# CAN.net
KiCad netlist of a schematic drawn in Altium Designer
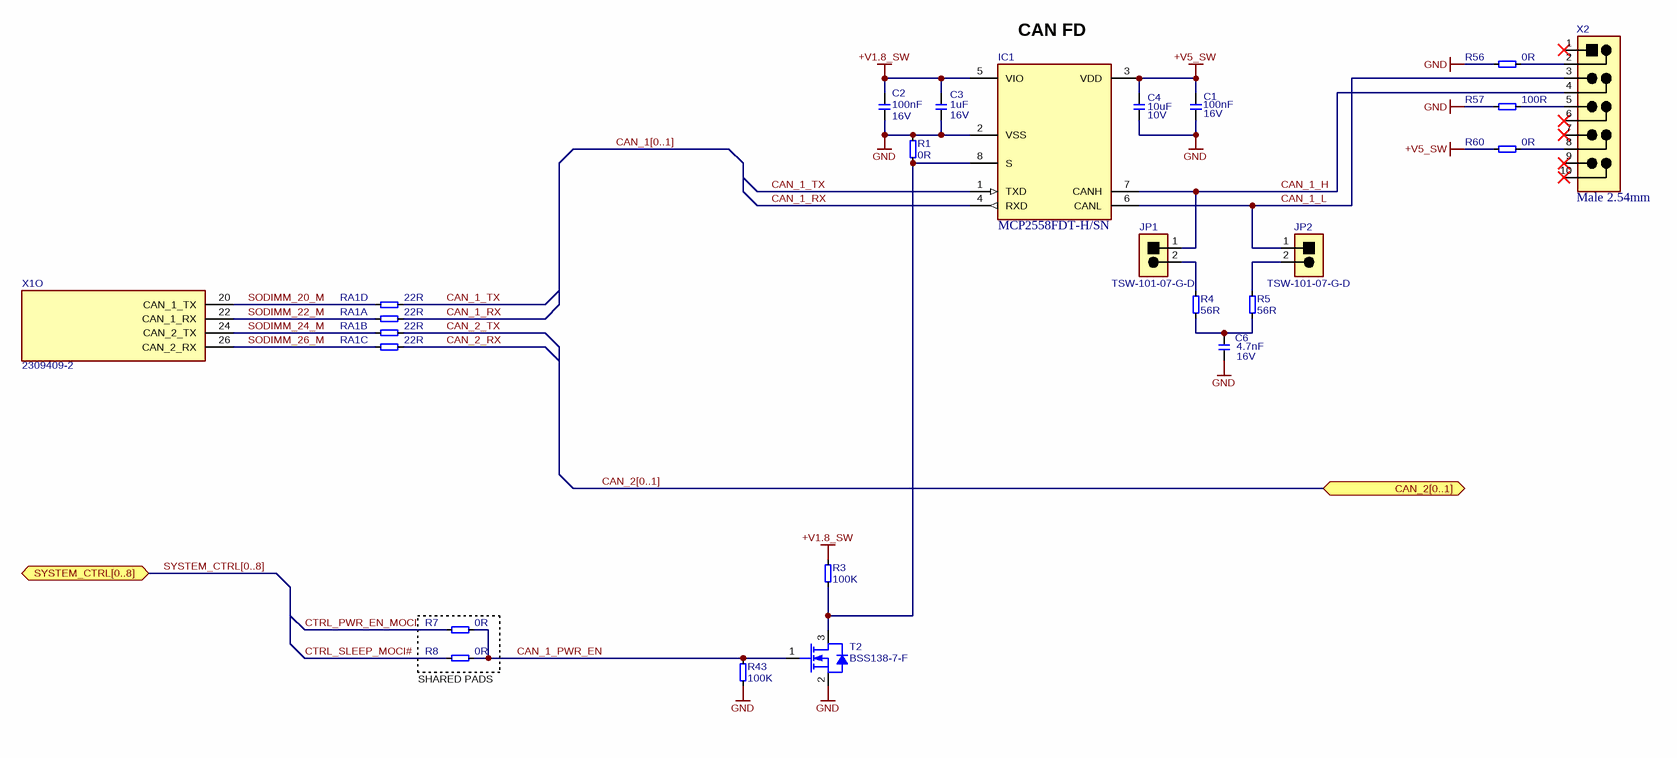
[diagram p0: CAN.SchDoc]

(export (version "E")
  (design (tool "Eeschema 10.0.6"))
  (components
    (comp (ref "C1")
      (value "100nF")
      (footprint "CAPC1005X60N")
      (description "Capacitor Ceramic X7R 100nF 16V 10% 0402")
      (fields (field (name "TOLERANCE") "10%") (field (name "RATING") "16V"))
      (libsource (lib "Dahlia Carrier Board") (part "C-X7R-100nF-16V-10%-0402"))
    )
    (comp (ref "C2")
      (value "100nF")
      (footprint "CAPC1005X60N")
      (description "Capacitor Ceramic X7R 100nF 16V 10% 0402")
      (fields (field (name "TOLERANCE") "10%") (field (name "RATING") "16V"))
      (libsource (lib "Dahlia Carrier Board") (part "C-X7R-100nF-16V-10%-0402"))
    )
    (comp (ref "C3")
      (value "1uF")
      (footprint "CAPC1005X60N")
      (description "Capacitor Ceramic X5R 1uF 16V 20% 0402")
      (fields (field (name "TOLERANCE") "20%") (field (name "RATING") "16V"))
      (libsource (lib "Dahlia Carrier Board") (part "C-X5R-1uF-16V-20%-0402"))
    )
    (comp (ref "C4")
      (value "10uF")
      (footprint "T_CAPC0603X33N")
      (description "Capacitor Ceramic X5R 10uF 10V 20% 0603")
      (fields (field (name "TOLERANCE") "20%") (field (name "RATING") "10V"))
      (libsource (lib "Dahlia Carrier Board") (part "C-X5R-10uF-10V-20%-0603"))
    )
    (comp (ref "C6")
      (value "4.7nF")
      (footprint "T_CAPC0603X33N")
      (description "Capacitor Ceramic X7R 4.7nF 16V 10% 0603")
      (fields (field (name "TOLERANCE") "10%") (field (name "RATING") "16V"))
      (libsource (lib "Dahlia Carrier Board") (part "C-X7R-4.7nF-16V-10%-0603"))
    )
    (comp (ref "IC1")
      (value "MCP2558FDT-H/SN")
      (footprint "IC-SOIC-8")
      (description "CAN FD Transceiver with Silent Mode")
      (fields (field (name "MANUFACTURER PART NO.") "MCP2558FDT-H/SN"))
      (libsource (lib "Dahlia Carrier Board") (part "IC-Microchip-MCP2558FDT-H/SN"))
    )
    (comp (ref "JP1")
      (value "TSW-101-07-G-D")
      (footprint "T_Samtec_TSW-101-07-G-D")
      (description "Header male, 1x2 Pins, 2.54 mm pitch")
      (libsource (lib "Dahlia Carrier Board") (part "CON-Samtec-TSW-101-07-G-D"))
    )
    (comp (ref "JP2")
      (value "TSW-101-07-G-D")
      (footprint "T_Samtec_TSW-101-07-G-D")
      (description "Header male, 1x2 Pins, 2.54 mm pitch")
      (libsource (lib "") (part "CON-Samtec-TSW-101-07-G-D_1"))
    )
    (comp (ref "R1")
      (value "0R")
      (footprint "T_RESC0603X30N")
      (description "Resistor 0 ohm 63mW 1% 0603")
      (fields (field (name "TOLERANCE") "1%"))
      (libsource (lib "Dahlia Carrier Board") (part "R-0R-63mW-1%-0603"))
    )
    (comp (ref "R3")
      (value "100K")
      (footprint "RESC1005X40N")
      (description "Resistor 100 Kohm 63mW 5% 0402")
      (fields (field (name "TOLERANCE") "5%"))
      (libsource (lib "Dahlia Carrier Board") (part "R-100K-63mW-5%-0402"))
    )
    (comp (ref "R4")
      (value "56R")
      (footprint "T_RESC0603X30N")
      (description "Resistor 56 ohm 125mW 1% 0603")
      (fields (field (name "TOLERANCE") "1%"))
      (libsource (lib "Dahlia Carrier Board") (part "R-56R-125mW-1%-0603"))
    )
    (comp (ref "R5")
      (value "56R")
      (footprint "T_RESC0603X30N")
      (description "Resistor 56 ohm 125mW 1% 0603")
      (fields (field (name "TOLERANCE") "1%"))
      (libsource (lib "Dahlia Carrier Board") (part "R-56R-125mW-1%-0603"))
    )
    (comp (ref "R7")
      (value "0R")
      (footprint "T_RESC0603X30N")
      (description "Resistor 0 ohm 63mW 1% 0603")
      (fields (field (name "TOLERANCE") "1%"))
      (libsource (lib "Dahlia Carrier Board") (part "R-0R-63mW-1%-0603"))
    )
    (comp (ref "R8")
      (value "0R")
      (footprint "T_RESC0603X30N")
      (description "Resistor 0 ohm 63mW 1% 0603")
      (fields (field (name "TOLERANCE") "1%"))
      (libsource (lib "Dahlia Carrier Board") (part "R-0R-63mW-1%-0603"))
    )
    (comp (ref "R43")
      (value "100K")
      (footprint "RESC1005X40N")
      (description "Resistor 100 Kohm 63mW 5% 0402")
      (fields (field (name "TOLERANCE") "5%"))
      (libsource (lib "Dahlia Carrier Board") (part "R-100K-63mW-5%-0402"))
    )
    (comp (ref "R56")
      (value "0R")
      (footprint "T_RESC0603X30N")
      (description "Resistor 0 ohm 63mW 1% 0603")
      (fields (field (name "TOLERANCE") "1%"))
      (libsource (lib "Dahlia Carrier Board") (part "R-0R-63mW-1%-0603"))
    )
    (comp (ref "R57")
      (value "100R")
      (footprint "T_RESC0603X30N")
      (description "Resistor 100 ohm 63mW 5% 0603")
      (fields (field (name "TOLERANCE") "5%"))
      (libsource (lib "Dahlia Carrier Board") (part "R-100R-63mW-5%-0603"))
    )
    (comp (ref "R60")
      (value "0R")
      (footprint "T_RESC0603X30N")
      (description "Resistor 0 ohm 63mW 1% 0603")
      (fields (field (name "TOLERANCE") "1%"))
      (libsource (lib "Dahlia Carrier Board") (part "R-0R-63mW-1%-0603"))
    )
    (comp (ref "RA1")
      (value "22R")
      (footprint "T_Resistor_Array_X4")
      (description "Resistor Array 22 R 63mW 5% 1206")
      (fields (field (name "TOLERANCE") "5%"))
      (libsource (lib "Dahlia Carrier Board") (part "RA-22R-63mW-5%-1206-div"))
    )
    (comp (ref "T2")
      (value "BSS138-7-F")
      (footprint "SOT95P237X112-3N")
      (description "N-channel MOSFET, BSS138-7-F")
      (fields (field (name "MANUFACTURER PART NO.") "BSS138-7-F"))
      (libsource (lib "Dahlia Carrier Board") (part "T-Diodes-BSS138-7-F"))
    )
    (comp (ref "X1")
      (value "2309409-2")
      (footprint "CON-TE-2309409-2-SOLDERABLE-STANDOFFS")
      (description "DDR4 SODIMM Socket, 260 pins, 5.2mm(H), 0.5mm Pitch")
      (libsource (lib "Dahlia Carrier Board") (part "CON-TE-2309409-2"))
    )
    (comp (ref "X2")
      (value "Male 2.54mm")
      (footprint "CON-Header-2x5-Male-2.54mm")
      (description "Header Male, 2x5 Pins, 2.54mm pitch")
      (fields (field (name "MANUFACTURER PART NO.") "77313-101-10LF"))
      (libsource (lib "Dahlia Carrier Board") (part "CON-Header-2x5-Male-2.54mm"))
    )
  )
  (nets
    (net (code "14") (name "+V1.8_SW") (class "Default")
      (node (ref "C2") (pin "2") (pinfunction "2_2") (pintype "passive"))
      (node (ref "C3") (pin "2") (pinfunction "2_2") (pintype "passive"))
      (node (ref "IC1") (pin "5") (pinfunction "VIO_5") (pintype "passive"))
      (node (ref "R3") (pin "1") (pinfunction "1_1") (pintype "passive"))
    )
    (net (code "15") (name "+V5_SW") (class "Default")
      (node (ref "C1") (pin "2") (pinfunction "2_2") (pintype "passive"))
      (node (ref "C4") (pin "2") (pinfunction "2_2") (pintype "passive"))
      (node (ref "IC1") (pin "3") (pinfunction "VDD_3") (pintype "power_in"))
      (node (ref "R60") (pin "2") (pinfunction "2_2") (pintype "passive"))
    )
    (net (code "17") (name "/CAN_1_H") (class "Default")
      (node (ref "IC1") (pin "7") (pinfunction "CANH_7") (pintype "passive"))
      (node (ref "JP1") (pin "1") (pinfunction "1_1") (pintype "passive"))
      (node (ref "X2") (pin "4") (pinfunction "4_4") (pintype "passive"))
    )
    (net (code "18") (name "/CAN_1_L") (class "Default")
      (node (ref "IC1") (pin "6") (pinfunction "CANL_6") (pintype "passive"))
      (node (ref "JP2") (pin "1") (pinfunction "1_1") (pintype "passive"))
      (node (ref "X2") (pin "3") (pinfunction "3_3") (pintype "passive"))
    )
    (net (code "19") (name "/CAN_1_PWR_EN") (class "Default")
      (node (ref "R43") (pin "1") (pinfunction "1_1") (pintype "passive"))
      (node (ref "R7") (pin "2") (pinfunction "2_2") (pintype "passive"))
      (node (ref "R8") (pin "2") (pinfunction "2_2") (pintype "passive"))
      (node (ref "T2") (pin "1") (pinfunction "G_1") (pintype "passive"))
    )
    (net (code "20") (name "/CAN_1_RX") (class "Default")
      (node (ref "IC1") (pin "4") (pinfunction "RXD_4") (pintype "output"))
      (node (ref "RA1") (pin "5") (pinfunction "5_5") (pintype "passive"))
    )
    (net (code "21") (name "/CAN_1_TX") (class "Default")
      (node (ref "IC1") (pin "1") (pinfunction "TXD_1") (pintype "input"))
      (node (ref "RA1") (pin "8") (pinfunction "8_8") (pintype "passive"))
    )
    (net (code "23") (name "/CAN_2_RX") (class "Default")
      (node (ref "RA1") (pin "7") (pinfunction "7_7") (pintype "passive"))
    )
    (net (code "24") (name "/CAN_2_TX") (class "Default")
      (node (ref "RA1") (pin "6") (pinfunction "6_6") (pintype "passive"))
    )
    (net (code "25") (name "/CTRL_PWR_EN_MOCI") (class "Default")
      (node (ref "R7") (pin "1") (pinfunction "1_1") (pintype "passive"))
    )
    (net (code "26") (name "/CTRL_SLEEP_MOCI#") (class "Default")
      (node (ref "R8") (pin "1") (pinfunction "1_1") (pintype "passive"))
    )
    (net (code "27") (name "/SODIMM_20_M") (class "Default")
      (node (ref "RA1") (pin "4") (pinfunction "4_4") (pintype "passive"))
      (node (ref "X1") (pin "20") (pinfunction "CAN_1_TX_20") (pintype "passive"))
    )
    (net (code "28") (name "/SODIMM_22_M") (class "Default")
      (node (ref "RA1") (pin "1") (pinfunction "1_1") (pintype "passive"))
      (node (ref "X1") (pin "22") (pinfunction "CAN_1_RX_22") (pintype "passive"))
    )
    (net (code "29") (name "/SODIMM_24_M") (class "Default")
      (node (ref "RA1") (pin "2") (pinfunction "2_2") (pintype "passive"))
      (node (ref "X1") (pin "24") (pinfunction "CAN_2_TX_24") (pintype "passive"))
    )
    (net (code "30") (name "/SODIMM_26_M") (class "Default")
      (node (ref "RA1") (pin "3") (pinfunction "3_3") (pintype "passive"))
      (node (ref "X1") (pin "26") (pinfunction "CAN_2_RX_26") (pintype "passive"))
    )
    (net (code "32") (name "GND") (class "Default")
      (node (ref "C1") (pin "1") (pinfunction "1_1") (pintype "passive"))
      (node (ref "C2") (pin "1") (pinfunction "1_1") (pintype "passive"))
      (node (ref "C3") (pin "1") (pinfunction "1_1") (pintype "passive"))
      (node (ref "C4") (pin "1") (pinfunction "1_1") (pintype "passive"))
      (node (ref "C6") (pin "1") (pinfunction "1_1") (pintype "passive"))
      (node (ref "IC1") (pin "2") (pinfunction "VSS_2") (pintype "power_in"))
      (node (ref "R1") (pin "2") (pinfunction "2_2") (pintype "passive"))
      (node (ref "R43") (pin "2") (pinfunction "2_2") (pintype "passive"))
      (node (ref "R56") (pin "2") (pinfunction "2_2") (pintype "passive"))
      (node (ref "R57") (pin "1") (pinfunction "1_1") (pintype "passive"))
      (node (ref "T2") (pin "2") (pinfunction "S_2") (pintype "passive"))
    )
    (net (code "33") (name "Net-(C6-Pad2)") (class "Default")
      (node (ref "C6") (pin "2") (pinfunction "2_2") (pintype "passive"))
      (node (ref "R4") (pin "1") (pinfunction "1_1") (pintype "passive"))
      (node (ref "R5") (pin "1") (pinfunction "1_1") (pintype "passive"))
    )
    (net (code "34") (name "Net-(IC1-S)") (class "Default")
      (node (ref "IC1") (pin "8") (pinfunction "S_8") (pintype "power_in"))
      (node (ref "R1") (pin "1") (pinfunction "1_1") (pintype "passive"))
      (node (ref "R3") (pin "2") (pinfunction "2_2") (pintype "passive"))
      (node (ref "T2") (pin "3") (pinfunction "D_3") (pintype "passive"))
    )
    (net (code "35") (name "Net-(JP1-Pad2)") (class "Default")
      (node (ref "JP1") (pin "2") (pinfunction "2_2") (pintype "passive"))
      (node (ref "R4") (pin "2") (pinfunction "2_2") (pintype "passive"))
    )
    (net (code "36") (name "Net-(JP2-Pad2)") (class "Default")
      (node (ref "JP2") (pin "2") (pinfunction "2_2") (pintype "passive"))
      (node (ref "R5") (pin "2") (pinfunction "2_2") (pintype "passive"))
    )
    (net (code "37") (name "Net-(R56-Pad1)") (class "Default")
      (node (ref "R56") (pin "1") (pinfunction "1_1") (pintype "passive"))
      (node (ref "X2") (pin "2") (pinfunction "2_2") (pintype "passive"))
    )
    (net (code "38") (name "Net-(R57-Pad2)") (class "Default")
      (node (ref "R57") (pin "2") (pinfunction "2_2") (pintype "passive"))
      (node (ref "X2") (pin "5") (pinfunction "5_5") (pintype "passive"))
    )
    (net (code "39") (name "Net-(R60-Pad1)") (class "Default")
      (node (ref "R60") (pin "1") (pinfunction "1_1") (pintype "passive"))
      (node (ref "X2") (pin "8") (pinfunction "8_8") (pintype "passive"))
    )
    (net (code "40") (name "unconnected-(X2-Pad1)") (class "Default")
      (node (ref "X2") (pin "1") (pinfunction "1_1") (pintype "passive+no_connect"))
    )
    (net (code "41") (name "unconnected-(X2-Pad6)") (class "Default")
      (node (ref "X2") (pin "6") (pinfunction "6_6") (pintype "passive+no_connect"))
    )
    (net (code "42") (name "unconnected-(X2-Pad7)") (class "Default")
      (node (ref "X2") (pin "7") (pinfunction "7_7") (pintype "passive+no_connect"))
    )
    (net (code "43") (name "unconnected-(X2-Pad9)") (class "Default")
      (node (ref "X2") (pin "9") (pinfunction "9_9") (pintype "passive+no_connect"))
    )
    (net (code "44") (name "unconnected-(X2-Pad10)") (class "Default")
      (node (ref "X2") (pin "10") (pinfunction "10_10") (pintype "passive+no_connect"))
    )
  )
)
